# design1.net
KiCad netlist of a schematic drawn in EAGLE
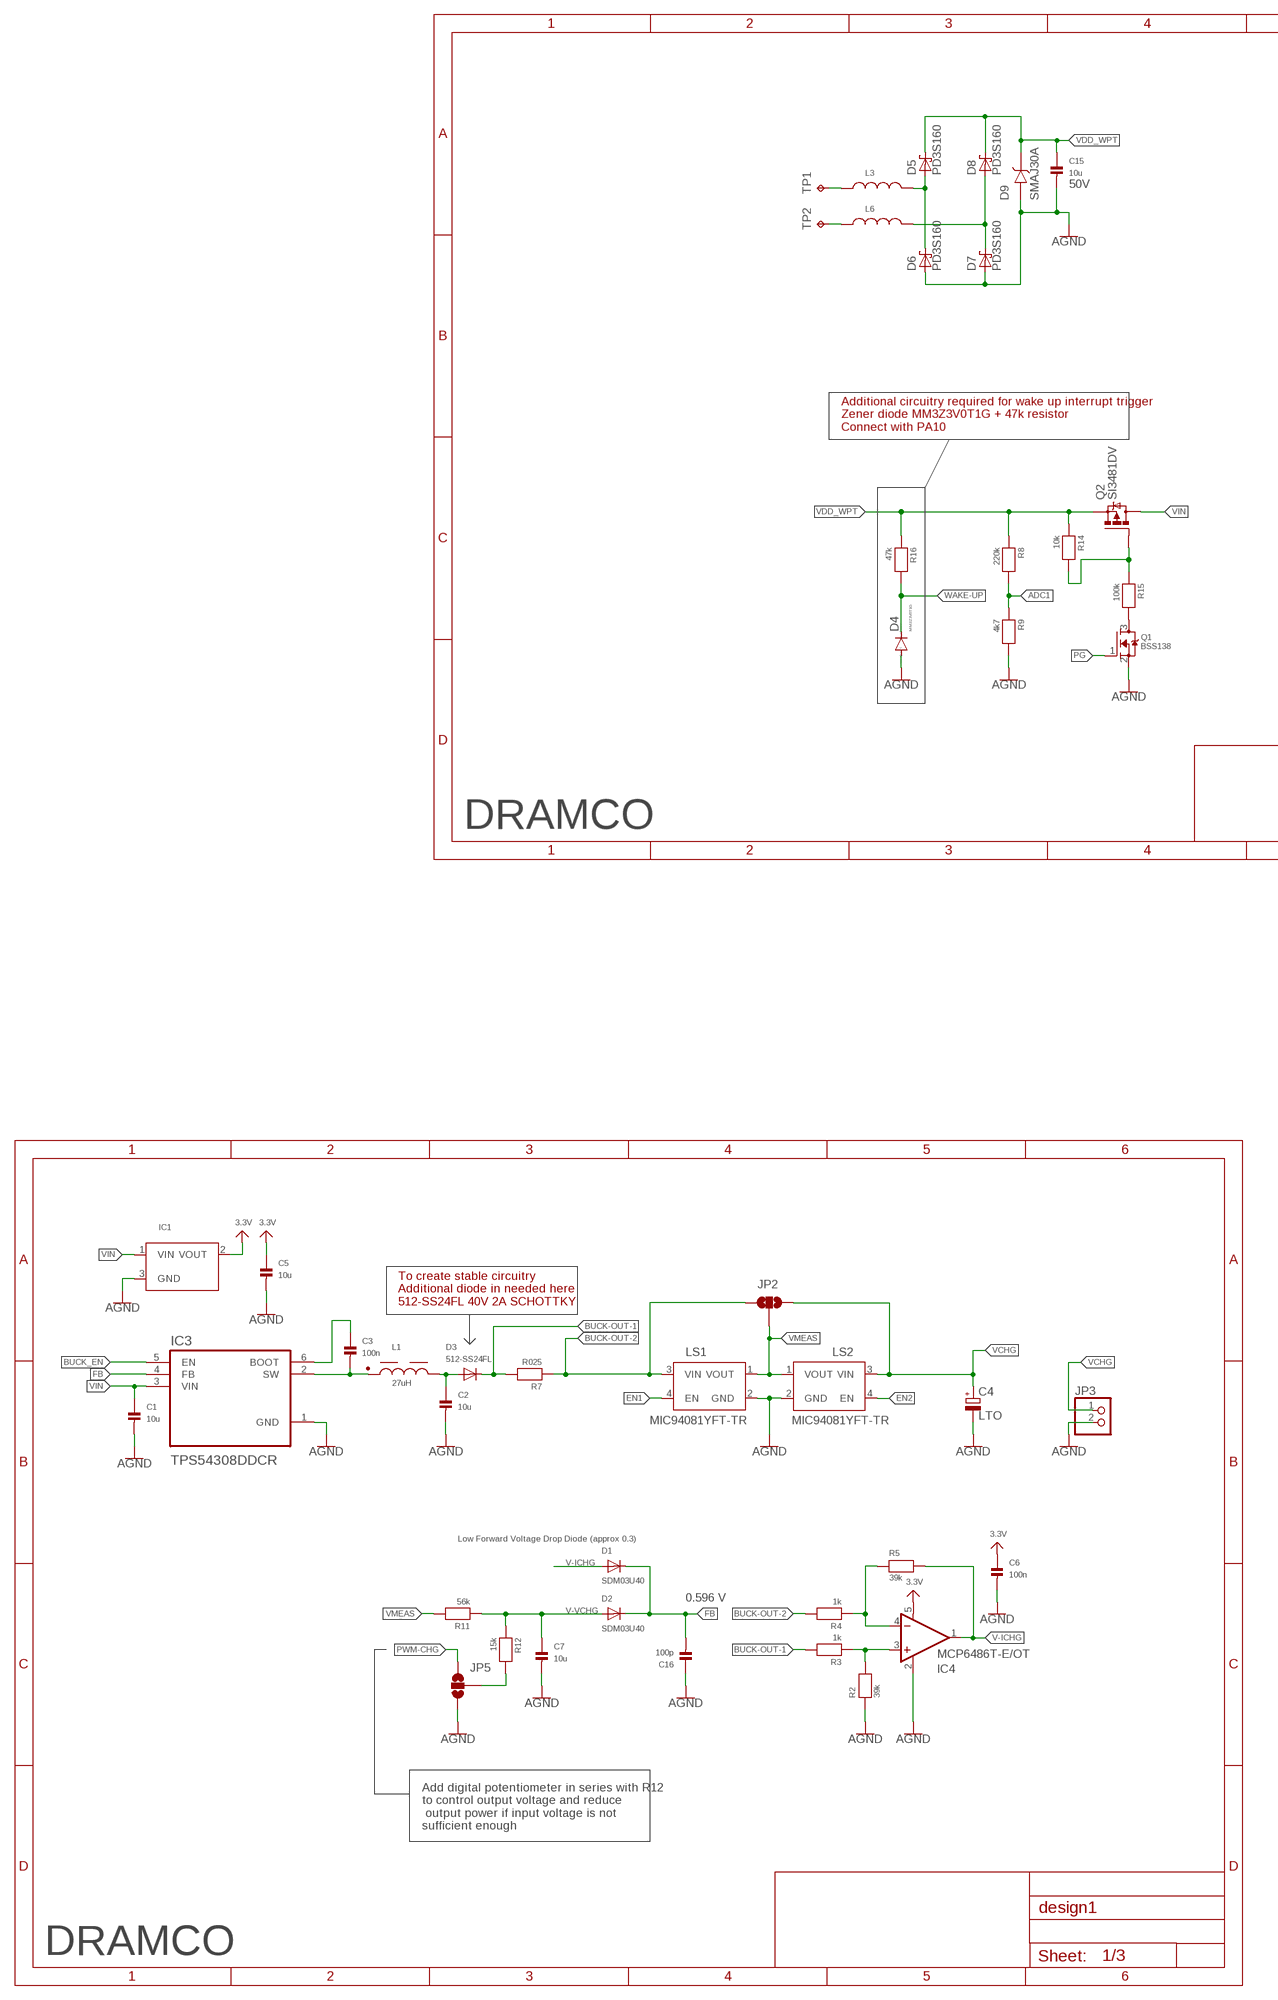
[diagram p0: schematic, sheet 1, part 1 of 2]
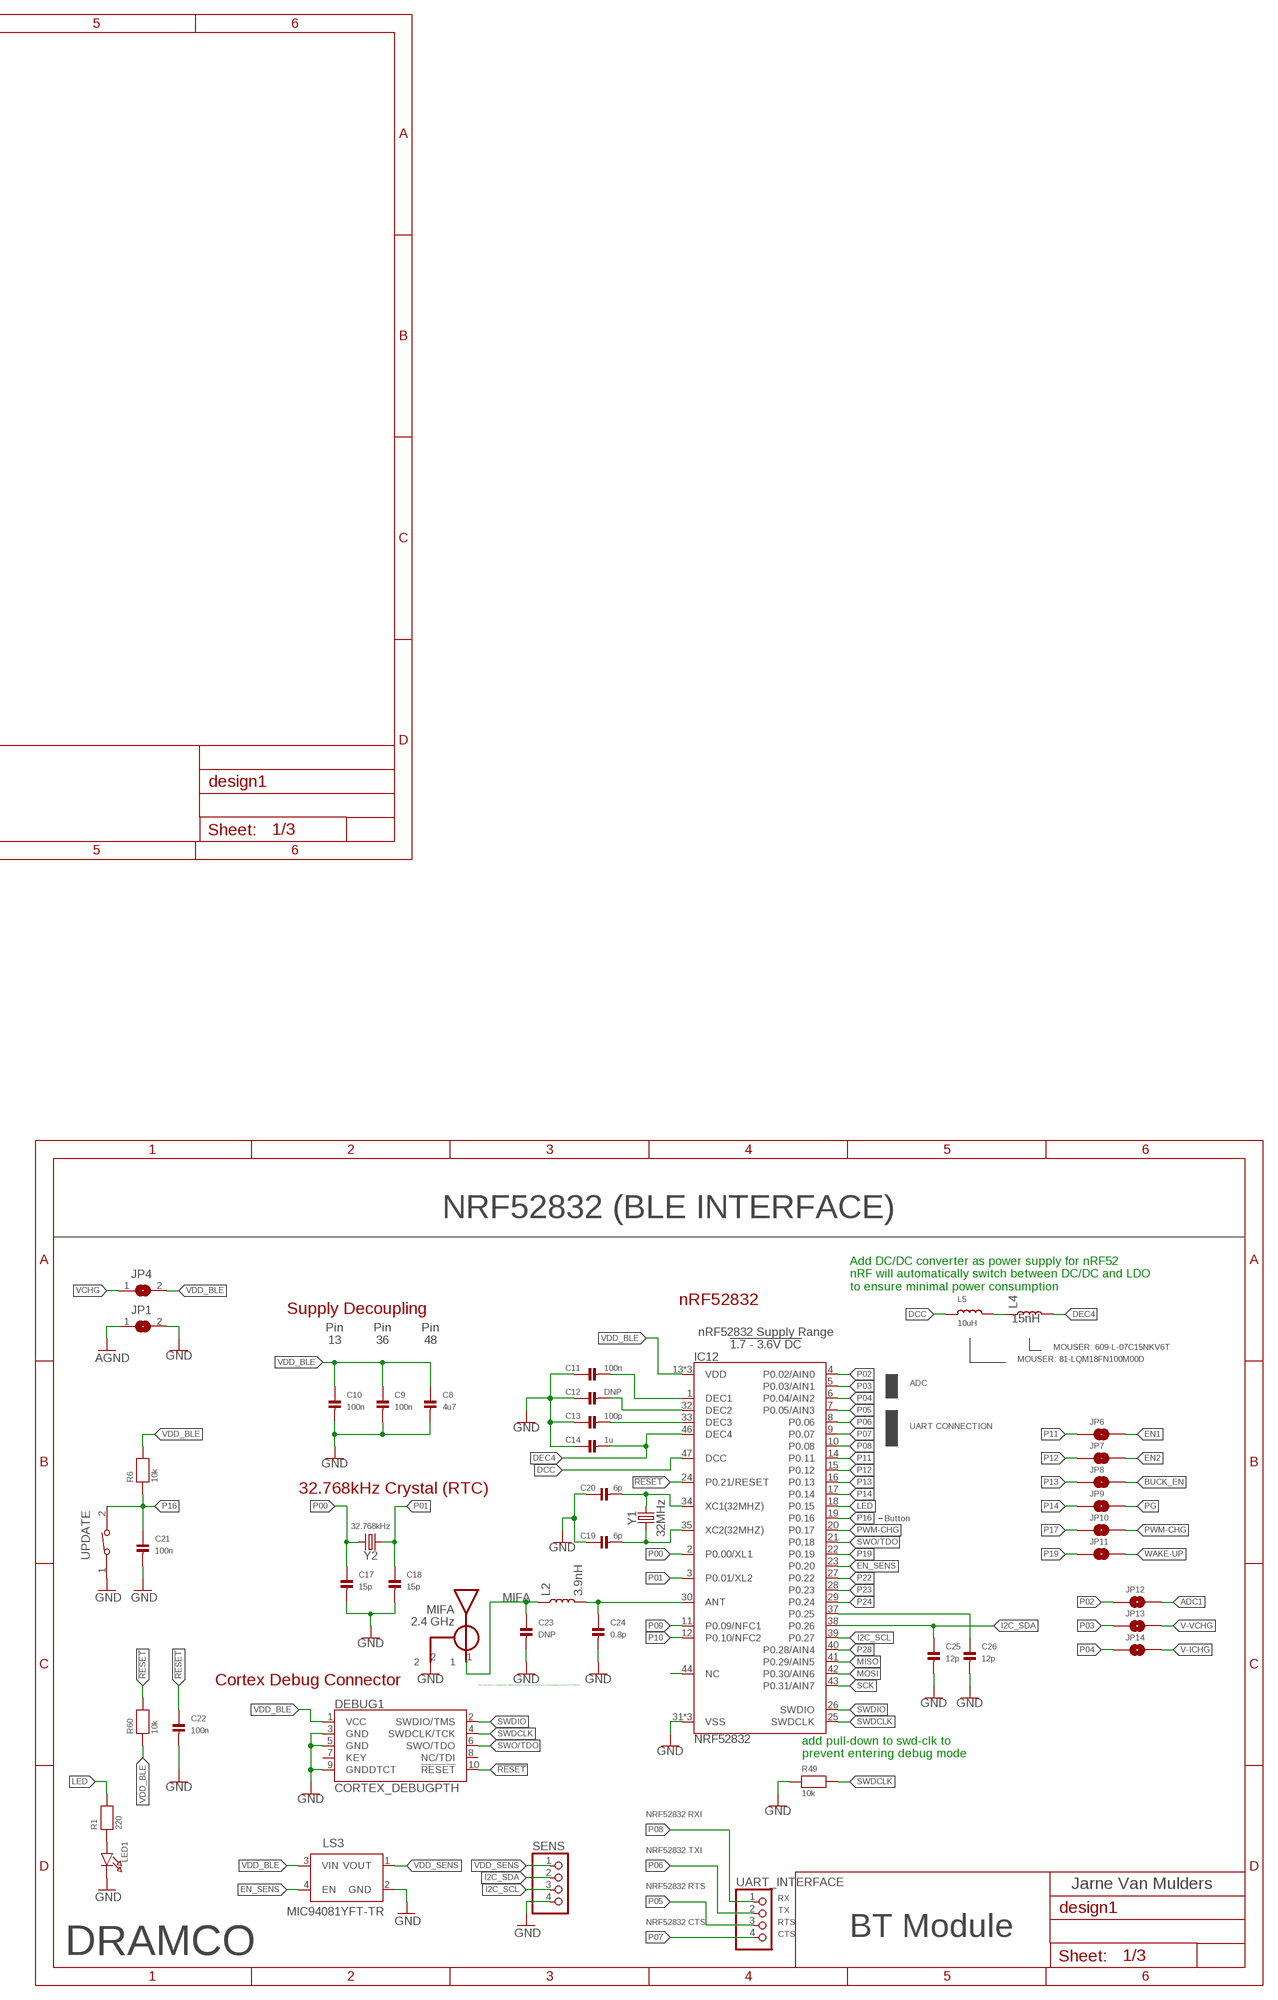
[diagram p1: schematic, sheet 1, part 2 of 2]

(export (version "E")
  (design (tool "Eeschema 10.0.6"))
  (components
    (comp (ref "C1")
      (value "10u")
      (footprint "eagle-import:0603")
      (libsource (lib "eagle-import") (part "CAP_CERAMIC0603"))
    )
    (comp (ref "C2")
      (value "10u")
      (footprint "eagle-import:0603")
      (libsource (lib "eagle-import") (part "CAP_CERAMIC0603"))
    )
    (comp (ref "C3")
      (value "100n")
      (footprint "eagle-import:0603")
      (libsource (lib "eagle-import") (part "CAP_CERAMIC0603"))
    )
    (comp (ref "C4")
      (value "LTO")
      (footprint "eagle-import:E5-10,5")
      (libsource (lib "eagle-import") (part "CPOL-EUE5-10.5"))
    )
    (comp (ref "C5")
      (value "10u")
      (footprint "eagle-import:0603")
      (libsource (lib "eagle-import") (part "CAP_CERAMIC0603"))
    )
    (comp (ref "C6")
      (value "100n")
      (footprint "eagle-import:0402")
      (libsource (lib "eagle-import") (part "CAP_CERAMIC0402"))
    )
    (comp (ref "C7")
      (value "10u")
      (footprint "eagle-import:0603")
      (libsource (lib "eagle-import") (part "CAP_CERAMIC0603"))
    )
    (comp (ref "C8")
      (value "4u7")
      (footprint "eagle-import:0603")
      (libsource (lib "eagle-import") (part "CAP_CERAMIC0603"))
    )
    (comp (ref "C9")
      (value "100n")
      (footprint "eagle-import:0402")
      (libsource (lib "eagle-import") (part "CAP_CERAMIC0402"))
    )
    (comp (ref "C10")
      (value "100n")
      (footprint "eagle-import:0402")
      (libsource (lib "eagle-import") (part "CAP_CERAMIC0402"))
    )
    (comp (ref "C11")
      (value "100n")
      (footprint "eagle-import:0402")
      (libsource (lib "eagle-import") (part "CAP_CERAMIC0402"))
    )
    (comp (ref "C12")
      (value "DNP")
      (footprint "eagle-import:0402")
      (libsource (lib "eagle-import") (part "CAP_CERAMIC0402"))
    )
    (comp (ref "C13")
      (value "100p")
      (footprint "eagle-import:0402")
      (libsource (lib "eagle-import") (part "CAP_CERAMIC0402"))
    )
    (comp (ref "C14")
      (value "1u")
      (footprint "eagle-import:0402")
      (libsource (lib "eagle-import") (part "CAP_CERAMIC0402"))
    )
    (comp (ref "C15")
      (value "10u")
      (footprint "eagle-import:1206")
      (libsource (lib "eagle-import") (part "CAP_CERAMIC1206"))
    )
    (comp (ref "C16")
      (value "100p")
      (footprint "eagle-import:0603")
      (libsource (lib "eagle-import") (part "CAP_CERAMIC0603"))
    )
    (comp (ref "C17")
      (value "15p")
      (footprint "eagle-import:0402")
      (libsource (lib "eagle-import") (part "CAP_CERAMIC0402"))
    )
    (comp (ref "C18")
      (value "15p")
      (footprint "eagle-import:0402")
      (libsource (lib "eagle-import") (part "CAP_CERAMIC0402"))
    )
    (comp (ref "C19")
      (value "6p")
      (footprint "eagle-import:0402")
      (libsource (lib "eagle-import") (part "CAP_CERAMIC0402"))
    )
    (comp (ref "C20")
      (value "6p")
      (footprint "eagle-import:0402")
      (libsource (lib "eagle-import") (part "CAP_CERAMIC0402"))
    )
    (comp (ref "C21")
      (value "100n")
      (footprint "eagle-import:0402")
      (libsource (lib "eagle-import") (part "CAP_CERAMIC0402"))
    )
    (comp (ref "C22")
      (value "100n")
      (footprint "eagle-import:0402")
      (libsource (lib "eagle-import") (part "CAP_CERAMIC0402"))
    )
    (comp (ref "C23")
      (value "DNP")
      (footprint "eagle-import:0402")
      (libsource (lib "eagle-import") (part "CAP_CERAMIC0402"))
    )
    (comp (ref "C24")
      (value "0.8p")
      (footprint "eagle-import:0402")
      (libsource (lib "eagle-import") (part "CAP_CERAMIC0402"))
    )
    (comp (ref "C25")
      (value "12p")
      (footprint "eagle-import:0402")
      (libsource (lib "eagle-import") (part "CAP_CERAMIC0402"))
    )
    (comp (ref "C26")
      (value "12p")
      (footprint "eagle-import:0402")
      (libsource (lib "eagle-import") (part "CAP_CERAMIC0402"))
    )
    (comp (ref "D1")
      (value "SDM03U40")
      (footprint "eagle-import:SOD-523")
      (libsource (lib "eagle-import") (part "DIODESOD-523"))
    )
    (comp (ref "D2")
      (value "SDM03U40")
      (footprint "eagle-import:SOD-523")
      (libsource (lib "eagle-import") (part "DIODESOD-523"))
    )
    (comp (ref "D3")
      (value "512-SS24FL")
      (footprint "eagle-import:SOD-123")
      (libsource (lib "eagle-import") (part "DIODESOD-123"))
    )
    (comp (ref "D4")
      (value "MM3Z3V0T1G")
      (footprint "eagle-import:SOD323-R")
      (libsource (lib "eagle-import") (part "DIODE-SOD323-R"))
    )
    (comp (ref "D5")
      (value "PD3S160")
      (footprint "eagle-import:POWERDI323")
      (libsource (lib "eagle-import") (part "PD3S160"))
    )
    (comp (ref "D6")
      (value "PD3S160")
      (footprint "eagle-import:POWERDI323")
      (libsource (lib "eagle-import") (part "PD3S160"))
    )
    (comp (ref "D7")
      (value "PD3S160")
      (footprint "eagle-import:POWERDI323")
      (libsource (lib "eagle-import") (part "PD3S160"))
    )
    (comp (ref "D8")
      (value "PD3S160")
      (footprint "eagle-import:POWERDI323")
      (libsource (lib "eagle-import") (part "PD3S160"))
    )
    (comp (ref "D9")
      (value "SMAJ30A")
      (footprint "eagle-import:DIOM5026X229N")
      (fields (field (name "MF") "Littelfuse"))
      (libsource (lib "eagle-import") (part "SMAJ30A"))
    )
    (comp (ref "DEBUG1")
      (value "CORTEX_DEBUGPTH")
      (footprint "eagle-import:2X5-PTH-1.27MM")
      (libsource (lib "eagle-import") (part "CORTEX_DEBUGPTH"))
    )
    (comp (ref "IC1")
      (value "VREG_SOT23")
      (footprint "eagle-import:SOT23-R")
      (libsource (lib "eagle-import") (part "VREG_SOT23"))
    )
    (comp (ref "IC3")
      (value "TPS54308DDCR")
      (footprint "eagle-import:SOT95P280X110-6N")
      (fields (field (name "MF") "Texas Instruments"))
      (libsource (lib "eagle-import") (part "TPS54308DDCR"))
    )
    (comp (ref "IC4")
      (value "MCP6486T-E/OT")
      (footprint "eagle-import:SOT23-5")
      (libsource (lib "eagle-import") (part "MCP6291T-E/OT"))
    )
    (comp (ref "IC12")
      (value "NRF52832")
      (footprint "eagle-import:QFN48-6X6MM")
      (libsource (lib "eagle-import") (part "NRF52832"))
    )
    (comp (ref "JP1")
      (value "SOLDERJUMPERREFLOW_NOPASTE")
      (footprint "eagle-import:SOLDERJUMPER_REFLOW_NOPASTE")
      (libsource (lib "eagle-import") (part "SOLDERJUMPERREFLOW_NOPASTE"))
    )
    (comp (ref "JP2")
      (value "JUMPER-SMT_3_NO_NO-SILK")
      (footprint "eagle-import:SMT-JUMPER_3_NO_NO-SILK")
      (libsource (lib "eagle-import") (part "JUMPER-SMT_3_NO_NO-SILK"))
    )
    (comp (ref "JP3")
      (value "HEADER-1X2ROUND")
      (footprint "eagle-import:1X02_ROUND")
      (libsource (lib "eagle-import") (part "HEADER-1X2ROUND"))
    )
    (comp (ref "JP4")
      (value "SOLDERJUMPERREFLOW_NOPASTE")
      (footprint "eagle-import:SOLDERJUMPER_REFLOW_NOPASTE")
      (libsource (lib "eagle-import") (part "SOLDERJUMPERREFLOW_NOPASTE"))
    )
    (comp (ref "JP5")
      (value "JUMPER-SMT_3_NO_NO-SILK")
      (footprint "eagle-import:SMT-JUMPER_3_NO_NO-SILK")
      (libsource (lib "eagle-import") (part "JUMPER-SMT_3_NO_NO-SILK"))
    )
    (comp (ref "JP6")
      (value "JUMPER-SMT_2_NO_NO-SILK")
      (footprint "eagle-import:SMT-JUMPER_2_NO_NO-SILK")
      (libsource (lib "eagle-import") (part "JUMPER-SMT_2_NO_NO-SILK"))
    )
    (comp (ref "JP7")
      (value "JUMPER-SMT_2_NO_NO-SILK")
      (footprint "eagle-import:SMT-JUMPER_2_NO_NO-SILK")
      (libsource (lib "eagle-import") (part "JUMPER-SMT_2_NO_NO-SILK"))
    )
    (comp (ref "JP8")
      (value "JUMPER-SMT_2_NO_NO-SILK")
      (footprint "eagle-import:SMT-JUMPER_2_NO_NO-SILK")
      (libsource (lib "eagle-import") (part "JUMPER-SMT_2_NO_NO-SILK"))
    )
    (comp (ref "JP9")
      (value "JUMPER-SMT_2_NO_NO-SILK")
      (footprint "eagle-import:SMT-JUMPER_2_NO_NO-SILK")
      (libsource (lib "eagle-import") (part "JUMPER-SMT_2_NO_NO-SILK"))
    )
    (comp (ref "JP10")
      (value "JUMPER-SMT_2_NO_NO-SILK")
      (footprint "eagle-import:SMT-JUMPER_2_NO_NO-SILK")
      (libsource (lib "eagle-import") (part "JUMPER-SMT_2_NO_NO-SILK"))
    )
    (comp (ref "JP11")
      (value "JUMPER-SMT_2_NO_NO-SILK")
      (footprint "eagle-import:SMT-JUMPER_2_NO_NO-SILK")
      (libsource (lib "eagle-import") (part "JUMPER-SMT_2_NO_NO-SILK"))
    )
    (comp (ref "JP12")
      (value "JUMPER-SMT_2_NO_NO-SILK")
      (footprint "eagle-import:SMT-JUMPER_2_NO_NO-SILK")
      (libsource (lib "eagle-import") (part "JUMPER-SMT_2_NO_NO-SILK"))
    )
    (comp (ref "JP13")
      (value "JUMPER-SMT_2_NO_NO-SILK")
      (footprint "eagle-import:SMT-JUMPER_2_NO_NO-SILK")
      (libsource (lib "eagle-import") (part "JUMPER-SMT_2_NO_NO-SILK"))
    )
    (comp (ref "JP14")
      (value "JUMPER-SMT_2_NO_NO-SILK")
      (footprint "eagle-import:SMT-JUMPER_2_NO_NO-SILK")
      (libsource (lib "eagle-import") (part "JUMPER-SMT_2_NO_NO-SILK"))
    )
    (comp (ref "L1")
      (value "27uH")
      (footprint "eagle-import:WE-PD_7332_7345_PLASTIC_BASE")
      (libsource (lib "eagle-import") (part "WE-PD_7332_PLASTIC_7447789127"))
    )
    (comp (ref "L2")
      (value "3.9nH")
      (footprint "eagle-import:0402")
      (libsource (lib "eagle-import") (part "INDUCTOR-0402-3.9NH"))
    )
    (comp (ref "L3")
      (value "WE-CAIR_4248_744912182")
      (footprint "eagle-import:WE-CAIR_4248")
      (libsource (lib "eagle-import") (part "WE-CAIR_4248_744912182"))
    )
    (comp (ref "L4")
      (value "15nH")
      (footprint "eagle-import:0402")
      (libsource (lib "eagle-import") (part "INDUCTOR-0402-3.9NH"))
    )
    (comp (ref "L5")
      (value "10uH")
      (footprint "eagle-import:_0603MP")
      (libsource (lib "eagle-import") (part "INDUCTOR_0603MP"))
    )
    (comp (ref "L6")
      (value "WE-CAIR_4248_744912182")
      (footprint "eagle-import:WE-CAIR_4248")
      (libsource (lib "eagle-import") (part "WE-CAIR_4248_744912182"))
    )
    (comp (ref "LED1")
      (value "LED0805")
      (footprint "eagle-import:CHIPLED_0805")
      (libsource (lib "eagle-import") (part "LED0805"))
    )
    (comp (ref "LS1")
      (value "MIC94081YFT-TR")
      (footprint "eagle-import:IC_MIC94081YFT-TR")
      (fields (field (name "MF") "Microchip"))
      (libsource (lib "eagle-import") (part "MIC94081YFT-TR"))
    )
    (comp (ref "LS2")
      (value "MIC94081YFT-TR")
      (footprint "eagle-import:IC_MIC94081YFT-TR")
      (fields (field (name "MF") "Microchip"))
      (libsource (lib "eagle-import") (part "MIC94081YFT-TR"))
    )
    (comp (ref "LS3")
      (value "MIC94081YFT-TR")
      (footprint "eagle-import:IC_MIC94081YFT-TR")
      (fields (field (name "MF") "Microchip"))
      (libsource (lib "eagle-import") (part "MIC94081YFT-TR"))
    )
    (comp (ref "Q1")
      (value "BSS138")
      (footprint "eagle-import:SOT23-R")
      (libsource (lib "eagle-import") (part "MOSFET-NREFLOW"))
    )
    (comp (ref "Q2")
      (value "SI3481DV")
      (footprint "eagle-import:TSOP-6.PAC")
      (libsource (lib "eagle-import") (part "SI3481DV"))
    )
    (comp (ref "R1")
      (value "220")
      (footprint "eagle-import:0603")
      (libsource (lib "eagle-import") (part "RESISTOR0603"))
    )
    (comp (ref "R2")
      (value "39k")
      (footprint "eagle-import:0603")
      (libsource (lib "eagle-import") (part "RESISTOR0603"))
    )
    (comp (ref "R3")
      (value "1k")
      (footprint "eagle-import:0603")
      (libsource (lib "eagle-import") (part "RESISTOR0603"))
    )
    (comp (ref "R4")
      (value "1k")
      (footprint "eagle-import:0603")
      (libsource (lib "eagle-import") (part "RESISTOR0603"))
    )
    (comp (ref "R5")
      (value "39k")
      (footprint "eagle-import:0603")
      (libsource (lib "eagle-import") (part "RESISTOR0603"))
    )
    (comp (ref "R6")
      (value "10k")
      (footprint "eagle-import:0402")
      (libsource (lib "eagle-import") (part "RESISTOR0402"))
    )
    (comp (ref "R7")
      (value "R025")
      (footprint "eagle-import:0603")
      (libsource (lib "eagle-import") (part "RESISTOR0603"))
    )
    (comp (ref "R8")
      (value "220k")
      (footprint "eagle-import:0603")
      (libsource (lib "eagle-import") (part "RESISTOR0603"))
    )
    (comp (ref "R9")
      (value "4k7")
      (footprint "eagle-import:0603")
      (libsource (lib "eagle-import") (part "RESISTOR0603"))
    )
    (comp (ref "R11")
      (value "56k")
      (footprint "eagle-import:0603")
      (libsource (lib "eagle-import") (part "RESISTOR0603"))
    )
    (comp (ref "R12")
      (value "15k")
      (footprint "eagle-import:0603")
      (libsource (lib "eagle-import") (part "RESISTOR0603"))
    )
    (comp (ref "R14")
      (value "10k")
      (footprint "eagle-import:0603")
      (libsource (lib "eagle-import") (part "RESISTOR0603"))
    )
    (comp (ref "R15")
      (value "100k")
      (footprint "eagle-import:0603")
      (libsource (lib "eagle-import") (part "RESISTOR0603"))
    )
    (comp (ref "R16")
      (value "47k")
      (footprint "eagle-import:0603")
      (libsource (lib "eagle-import") (part "RESISTOR0603"))
    )
    (comp (ref "R49")
      (value "10k")
      (footprint "eagle-import:0402")
      (libsource (lib "eagle-import") (part "RESISTOR0402"))
    )
    (comp (ref "R60")
      (value "10k")
      (footprint "eagle-import:0402")
      (libsource (lib "eagle-import") (part "RESISTOR0402"))
    )
    (comp (ref "SENS")
      (value "HEADER-1X4ROUND")
      (footprint "eagle-import:1X04_ROUND")
      (libsource (lib "eagle-import") (part "HEADER-1X4ROUND"))
    )
    (comp (ref "TP1")
      (value "TPTP20SQ")
      (footprint "eagle-import:TP20SQ")
      (libsource (lib "eagle-import") (part "TPTP20SQ"))
    )
    (comp (ref "TP2")
      (value "TPTP20SQ")
      (footprint "eagle-import:TP20SQ")
      (libsource (lib "eagle-import") (part "TPTP20SQ"))
    )
    (comp (ref "U$18")
      (value "BLE-ANT")
      (footprint "eagle-import:ANT-2G4")
      (libsource (lib "eagle-import") (part "BLE-ANT"))
    )
    (comp (ref "UART_INTERFACE")
      (value "HEADER-1X4ROUND")
      (footprint "eagle-import:1X04_ROUND")
      (libsource (lib "eagle-import") (part "HEADER-1X4ROUND"))
    )
    (comp (ref "UPDATE")
      (value "434111043826")
      (footprint "eagle-import:434111043826")
      (libsource (lib "eagle-import") (part "434111043826"))
    )
    (comp (ref "Y1")
      (value "32MHz")
      (footprint "eagle-import:CRYSTAL-SMD-2.0X1.6MM")
      (libsource (lib "eagle-import") (part "CRYSTAL-32MHZ-SMD-2.0X1.6MM"))
    )
    (comp (ref "Y2")
      (value "32.768kHz")
      (footprint "eagle-import:CRYSTAL-SMD-3.2X1.5MM")
      (libsource (lib "eagle-import") (part "CRYSTAL-32.768KHZSMD-3.2X1.5"))
    )
  )
  (nets
    (net (code "1") (name "3.3V") (class "Default")
      (node (ref "C5") (pin "1") (pinfunction "P$1_1") (pintype "passive"))
      (node (ref "C6") (pin "1") (pinfunction "P$1_1") (pintype "passive"))
      (node (ref "IC1") (pin "2") (pinfunction "VOUT_2") (pintype "power_in"))
      (node (ref "IC4") (pin "5") (pinfunction "V+_5") (pintype "power_in"))
    )
    (net (code "2") (name "ADC1") (class "Default")
      (node (ref "JP12") (pin "2") (pinfunction "2_2") (pintype "passive"))
      (node (ref "R8") (pin "2") (pinfunction "2_2") (pintype "passive"))
      (node (ref "R9") (pin "1") (pinfunction "1_1") (pintype "passive"))
    )
    (net (code "3") (name "AGND") (class "Default")
      (node (ref "C1") (pin "2") (pinfunction "P$2_2") (pintype "passive"))
      (node (ref "C15") (pin "2") (pinfunction "P$2_2") (pintype "passive"))
      (node (ref "C16") (pin "1") (pinfunction "P$1_1") (pintype "passive"))
      (node (ref "C2") (pin "2") (pinfunction "P$2_2") (pintype "passive"))
      (node (ref "C4") (pin "-") (pinfunction "-_-") (pintype "passive"))
      (node (ref "C5") (pin "2") (pinfunction "P$2_2") (pintype "passive"))
      (node (ref "C6") (pin "2") (pinfunction "P$2_2") (pintype "passive"))
      (node (ref "C7") (pin "2") (pinfunction "P$2_2") (pintype "passive"))
      (node (ref "D4") (pin "A") (pinfunction "A_A") (pintype "passive"))
      (node (ref "D6") (pin "A") (pinfunction "A_A") (pintype "passive"))
      (node (ref "D7") (pin "A") (pinfunction "A_A") (pintype "passive"))
      (node (ref "D9") (pin "A") (pinfunction "A_A") (pintype "passive"))
      (node (ref "IC1") (pin "3") (pinfunction "GND_3") (pintype "power_in"))
      (node (ref "IC3") (pin "1") (pinfunction "GND_1") (pintype "power_in"))
      (node (ref "IC4") (pin "2") (pinfunction "V-_2") (pintype "power_in"))
      (node (ref "JP1") (pin "1") (pinfunction "1_1") (pintype "passive"))
      (node (ref "JP3") (pin "2") (pinfunction "2_2") (pintype "passive"))
      (node (ref "JP5") (pin "1") (pinfunction "1_1") (pintype "passive"))
      (node (ref "LS1") (pin "2") (pinfunction "GND_2") (pintype "power_in"))
      (node (ref "LS2") (pin "2") (pinfunction "GND_2") (pintype "power_in"))
      (node (ref "Q1") (pin "2") (pinfunction "S_2") (pintype "bidirectional"))
      (node (ref "R2") (pin "1") (pinfunction "1_1") (pintype "passive"))
      (node (ref "R9") (pin "2") (pinfunction "2_2") (pintype "passive"))
    )
    (net (code "4") (name "BUCK-OUT-1") (class "Default")
      (node (ref "D3") (pin "C") (pinfunction "C_C") (pintype "passive"))
      (node (ref "R3") (pin "2") (pinfunction "2_2") (pintype "passive"))
      (node (ref "R7") (pin "2") (pinfunction "2_2") (pintype "passive"))
    )
    (net (code "5") (name "BUCK-OUT-2") (class "Default")
      (node (ref "JP2") (pin "1") (pinfunction "1_1") (pintype "passive"))
      (node (ref "LS1") (pin "3") (pinfunction "VIN_3") (pintype "input"))
      (node (ref "R4") (pin "2") (pinfunction "2_2") (pintype "passive"))
      (node (ref "R7") (pin "1") (pinfunction "1_1") (pintype "passive"))
    )
    (net (code "6") (name "BUCK_EN") (class "Default")
      (node (ref "IC3") (pin "5") (pinfunction "EN_5") (pintype "input"))
      (node (ref "JP8") (pin "2") (pinfunction "2_2") (pintype "passive"))
    )
    (net (code "7") (name "DCC") (class "Default")
      (node (ref "IC12") (pin "47") (pinfunction "DCC_47") (pintype "bidirectional"))
      (node (ref "L5") (pin "1") (pinfunction "1_1") (pintype "passive"))
    )
    (net (code "8") (name "DEC4") (class "Default")
      (node (ref "C14") (pin "2") (pinfunction "P$2_2") (pintype "passive"))
      (node (ref "IC12") (pin "46") (pinfunction "DEC4_46") (pintype "bidirectional"))
      (node (ref "L4") (pin "2") (pinfunction "2_2") (pintype "passive"))
    )
    (net (code "9") (name "EN1") (class "Default")
      (node (ref "JP6") (pin "2") (pinfunction "2_2") (pintype "passive"))
      (node (ref "LS1") (pin "4") (pinfunction "EN_4") (pintype "input"))
    )
    (net (code "10") (name "EN2") (class "Default")
      (node (ref "JP7") (pin "2") (pinfunction "2_2") (pintype "passive"))
      (node (ref "LS2") (pin "4") (pinfunction "EN_4") (pintype "input"))
    )
    (net (code "11") (name "EN_SENS") (class "Default")
      (node (ref "IC12") (pin "23") (pinfunction "P0.20_23") (pintype "bidirectional"))
      (node (ref "LS3") (pin "4") (pinfunction "EN_4") (pintype "input"))
    )
    (net (code "12") (name "FB") (class "Default")
      (node (ref "C16") (pin "2") (pinfunction "P$2_2") (pintype "passive"))
      (node (ref "D1") (pin "K") (pinfunction "C_K") (pintype "passive"))
      (node (ref "D2") (pin "K") (pinfunction "C_K") (pintype "passive"))
      (node (ref "IC3") (pin "4") (pinfunction "FB_4") (pintype "input"))
    )
    (net (code "13") (name "GND") (class "Default")
      (node (ref "C10") (pin "2") (pinfunction "P$2_2") (pintype "passive"))
      (node (ref "C11") (pin "1") (pinfunction "P$1_1") (pintype "passive"))
      (node (ref "C12") (pin "1") (pinfunction "P$1_1") (pintype "passive"))
      (node (ref "C13") (pin "1") (pinfunction "P$1_1") (pintype "passive"))
      (node (ref "C14") (pin "1") (pinfunction "P$1_1") (pintype "passive"))
      (node (ref "C17") (pin "2") (pinfunction "P$2_2") (pintype "passive"))
      (node (ref "C18") (pin "2") (pinfunction "P$2_2") (pintype "passive"))
      (node (ref "C19") (pin "1") (pinfunction "P$1_1") (pintype "passive"))
      (node (ref "C20") (pin "1") (pinfunction "P$1_1") (pintype "passive"))
      (node (ref "C21") (pin "2") (pinfunction "P$2_2") (pintype "passive"))
      (node (ref "C22") (pin "2") (pinfunction "P$2_2") (pintype "passive"))
      (node (ref "C23") (pin "2") (pinfunction "P$2_2") (pintype "passive"))
      (node (ref "C24") (pin "2") (pinfunction "P$2_2") (pintype "passive"))
      (node (ref "C25") (pin "2") (pinfunction "P$2_2") (pintype "passive"))
      (node (ref "C26") (pin "2") (pinfunction "P$2_2") (pintype "passive"))
      (node (ref "C8") (pin "2") (pinfunction "P$2_2") (pintype "passive"))
      (node (ref "C9") (pin "2") (pinfunction "P$2_2") (pintype "passive"))
      (node (ref "DEBUG1") (pin "3") (pinfunction "GND_3") (pintype "bidirectional"))
      (node (ref "DEBUG1") (pin "5") (pinfunction "GND_5") (pintype "bidirectional"))
      (node (ref "DEBUG1") (pin "9") (pinfunction "GNDDTCT_9") (pintype "bidirectional"))
      (node (ref "IC12") (pin "31") (pinfunction "VSS_31") (pintype "bidirectional"))
      (node (ref "IC12") (pin "45") (pinfunction "VSS_45") (pintype "bidirectional"))
      (node (ref "IC12") (pin "EP") (pinfunction "VSS_EP") (pintype "bidirectional"))
      (node (ref "JP1") (pin "2") (pinfunction "2_2") (pintype "passive"))
      (node (ref "LED1") (pin "C") (pinfunction "C_C") (pintype "passive"))
      (node (ref "LS3") (pin "2") (pinfunction "GND_2") (pintype "power_in"))
      (node (ref "R49") (pin "1") (pinfunction "1_1") (pintype "passive"))
      (node (ref "SENS") (pin "4") (pinfunction "4_4") (pintype "passive"))
      (node (ref "U$18") (pin "2") (pinfunction "2_2") (pintype "bidirectional"))
      (node (ref "UPDATE") (pin "1") (pinfunction "1_1") (pintype "passive"))
    )
    (net (code "14") (name "I2C_SCL") (class "Default")
      (node (ref "IC12") (pin "39") (pinfunction "P0.27_39") (pintype "bidirectional"))
      (node (ref "SENS") (pin "3") (pinfunction "3_3") (pintype "passive"))
    )
    (net (code "15") (name "I2C_SDA") (class "Default")
      (node (ref "C25") (pin "1") (pinfunction "P$1_1") (pintype "passive"))
      (node (ref "IC12") (pin "38") (pinfunction "P0.26_38") (pintype "bidirectional"))
      (node (ref "SENS") (pin "2") (pinfunction "2_2") (pintype "passive"))
    )
    (net (code "16") (name "LED") (class "Default")
      (node (ref "IC12") (pin "18") (pinfunction "P0.15_18") (pintype "bidirectional"))
      (node (ref "R1") (pin "2") (pinfunction "2_2") (pintype "passive"))
    )
    (net (code "17") (name "MIFA") (class "Default")
      (node (ref "C23") (pin "1") (pinfunction "P$1_1") (pintype "passive"))
      (node (ref "L2") (pin "1") (pinfunction "1_1") (pintype "passive"))
      (node (ref "U$18") (pin "1") (pinfunction "1_1") (pintype "bidirectional"))
    )
    (net (code "18") (name "MISO") (class "Default")
      (node (ref "IC12") (pin "41") (pinfunction "P0.29/AIN5_41") (pintype "bidirectional"))
    )
    (net (code "19") (name "MOSI") (class "Default")
      (node (ref "IC12") (pin "42") (pinfunction "P0.30/AIN6_42") (pintype "bidirectional"))
    )
    (net (code "20") (name "Net-(C2-P$1)") (class "Default")
      (node (ref "C2") (pin "1") (pinfunction "P$1_1") (pintype "passive"))
      (node (ref "D3") (pin "A") (pinfunction "A_A") (pintype "passive"))
      (node (ref "L1") (pin "2") (pinfunction "2_2") (pintype "passive"))
    )
    (net (code "21") (name "Net-(C3-P$1)") (class "Default")
      (node (ref "C3") (pin "1") (pinfunction "P$1_1") (pintype "passive"))
      (node (ref "IC3") (pin "6") (pinfunction "BOOT_6") (pintype "output"))
    )
    (net (code "22") (name "Net-(C3-P$2)") (class "Default")
      (node (ref "C3") (pin "2") (pinfunction "P$2_2") (pintype "passive"))
      (node (ref "IC3") (pin "2") (pinfunction "SW_2") (pintype "output"))
      (node (ref "L1") (pin "1") (pinfunction "1_1") (pintype "passive"))
    )
    (net (code "23") (name "Net-(C11-P$2)") (class "Default")
      (node (ref "C11") (pin "2") (pinfunction "P$2_2") (pintype "passive"))
      (node (ref "IC12") (pin "1") (pinfunction "DEC1_1") (pintype "bidirectional"))
    )
    (net (code "24") (name "Net-(C12-P$2)") (class "Default")
      (node (ref "C12") (pin "2") (pinfunction "P$2_2") (pintype "passive"))
      (node (ref "IC12") (pin "32") (pinfunction "DEC2_32") (pintype "bidirectional"))
    )
    (net (code "25") (name "Net-(C13-P$2)") (class "Default")
      (node (ref "C13") (pin "2") (pinfunction "P$2_2") (pintype "passive"))
      (node (ref "IC12") (pin "33") (pinfunction "DEC3_33") (pintype "bidirectional"))
    )
    (net (code "26") (name "Net-(C19-P$2)") (class "Default")
      (node (ref "C19") (pin "2") (pinfunction "P$2_2") (pintype "passive"))
      (node (ref "IC12") (pin "35") (pinfunction "XC2(32MHZ)_35") (pintype "bidirectional"))
      (node (ref "Y1") (pin "1") (pinfunction "1_1") (pintype "passive"))
    )
    (net (code "27") (name "Net-(C20-P$2)") (class "Default")
      (node (ref "C20") (pin "2") (pinfunction "P$2_2") (pintype "passive"))
      (node (ref "IC12") (pin "34") (pinfunction "XC1(32MHZ)_34") (pintype "bidirectional"))
      (node (ref "Y1") (pin "3") (pinfunction "2_3") (pintype "passive"))
    )
    (net (code "28") (name "Net-(C24-P$1)") (class "Default")
      (node (ref "C24") (pin "1") (pinfunction "P$1_1") (pintype "passive"))
      (node (ref "IC12") (pin "30") (pinfunction "ANT_30") (pintype "bidirectional"))
      (node (ref "L2") (pin "2") (pinfunction "2_2") (pintype "passive"))
    )
    (net (code "29") (name "Net-(C26-P$1)") (class "Default")
      (node (ref "C26") (pin "1") (pinfunction "P$1_1") (pintype "passive"))
      (node (ref "IC12") (pin "37") (pinfunction "P0.25_37") (pintype "bidirectional"))
    )
    (net (code "30") (name "Net-(D5-PadA)") (class "Default")
      (node (ref "D5") (pin "A") (pinfunction "A_A") (pintype "passive"))
      (node (ref "D6") (pin "C") (pinfunction "C_C") (pintype "passive"))
      (node (ref "L3") (pin "2") (pinfunction "2_2") (pintype "passive"))
    )
    (net (code "31") (name "Net-(D7-PadC)") (class "Default")
      (node (ref "D7") (pin "C") (pinfunction "C_C") (pintype "passive"))
      (node (ref "D8") (pin "A") (pinfunction "A_A") (pintype "passive"))
      (node (ref "L6") (pin "2") (pinfunction "2_2") (pintype "passive"))
    )
    (net (code "32") (name "Net-(IC4-+IN)") (class "Default")
      (node (ref "IC4") (pin "3") (pinfunction "+IN_3") (pintype "input"))
      (node (ref "R2") (pin "2") (pinfunction "2_2") (pintype "passive"))
      (node (ref "R3") (pin "1") (pinfunction "1_1") (pintype "passive"))
    )
    (net (code "33") (name "Net-(IC4--IN)") (class "Default")
      (node (ref "IC4") (pin "4") (pinfunction "-IN_4") (pintype "input"))
      (node (ref "R4") (pin "1") (pinfunction "1_1") (pintype "passive"))
      (node (ref "R5") (pin "1") (pinfunction "1_1") (pintype "passive"))
    )
    (net (code "34") (name "Net-(JP5-Pad2)") (class "Default")
      (node (ref "JP5") (pin "2") (pinfunction "2_2") (pintype "passive"))
      (node (ref "R12") (pin "2") (pinfunction "2_2") (pintype "passive"))
    )
    (net (code "35") (name "Net-(L3-Pad1)") (class "Default")
      (node (ref "L3") (pin "1") (pinfunction "1_1") (pintype "passive"))
      (node (ref "TP1") (pin "TP") (pinfunction "TP_TP") (pintype "input"))
    )
    (net (code "36") (name "Net-(L4-Pad1)") (class "Default")
      (node (ref "L4") (pin "1") (pinfunction "1_1") (pintype "passive"))
      (node (ref "L5") (pin "2") (pinfunction "2_2") (pintype "passive"))
    )
    (net (code "37") (name "Net-(L6-Pad1)") (class "Default")
      (node (ref "L6") (pin "1") (pinfunction "1_1") (pintype "passive"))
      (node (ref "TP2") (pin "TP") (pinfunction "TP_TP") (pintype "input"))
    )
    (net (code "38") (name "Net-(LED1-PadA)") (class "Default")
      (node (ref "LED1") (pin "A") (pinfunction "A_A") (pintype "passive"))
      (node (ref "R1") (pin "1") (pinfunction "1_1") (pintype "passive"))
    )
    (net (code "39") (name "Net-(Q1-D)") (class "Default")
      (node (ref "Q1") (pin "3") (pinfunction "D_3") (pintype "bidirectional"))
      (node (ref "R15") (pin "2") (pinfunction "2_2") (pintype "passive"))
    )
    (net (code "40") (name "Net-(Q2-G)") (class "Default")
      (node (ref "Q2") (pin "3") (pinfunction "G_3") (pintype "passive"))
      (node (ref "R14") (pin "2") (pinfunction "2_2") (pintype "passive"))
      (node (ref "R15") (pin "1") (pinfunction "1_1") (pintype "passive"))
    )
    (net (code "41") (name "P00") (class "Default")
      (node (ref "C17") (pin "1") (pinfunction "P$1_1") (pintype "passive"))
      (node (ref "IC12") (pin "2") (pinfunction "P0.00/XL1_2") (pintype "bidirectional"))
      (node (ref "Y2") (pin "P$2") (pinfunction "2_P$2") (pintype "passive"))
    )
    (net (code "42") (name "P01") (class "Default")
      (node (ref "C18") (pin "1") (pinfunction "P$1_1") (pintype "passive"))
      (node (ref "IC12") (pin "3") (pinfunction "P0.01/XL2_3") (pintype "bidirectional"))
      (node (ref "Y2") (pin "P$1") (pinfunction "1_P$1") (pintype "passive"))
    )
    (net (code "43") (name "P02") (class "Default")
      (node (ref "IC12") (pin "4") (pinfunction "P0.02/AIN0_4") (pintype "bidirectional"))
      (node (ref "JP12") (pin "1") (pinfunction "1_1") (pintype "passive"))
    )
    (net (code "44") (name "P03") (class "Default")
      (node (ref "IC12") (pin "5") (pinfunction "P0.03/AIN1_5") (pintype "bidirectional"))
      (node (ref "JP13") (pin "1") (pinfunction "1_1") (pintype "passive"))
    )
    (net (code "45") (name "P04") (class "Default")
      (node (ref "IC12") (pin "6") (pinfunction "P0.04/AIN2_6") (pintype "bidirectional"))
      (node (ref "JP14") (pin "1") (pinfunction "1_1") (pintype "passive"))
    )
    (net (code "46") (name "P05") (class "Default")
      (node (ref "IC12") (pin "7") (pinfunction "P0.05/AIN3_7") (pintype "bidirectional"))
      (node (ref "UART_INTERFACE") (pin "3") (pinfunction "3_3") (pintype "passive"))
    )
    (net (code "47") (name "P06") (class "Default")
      (node (ref "IC12") (pin "8") (pinfunction "P0.06_8") (pintype "bidirectional"))
      (node (ref "UART_INTERFACE") (pin "2") (pinfunction "2_2") (pintype "passive"))
    )
    (net (code "48") (name "P07") (class "Default")
      (node (ref "IC12") (pin "9") (pinfunction "P0.07_9") (pintype "bidirectional"))
      (node (ref "UART_INTERFACE") (pin "4") (pinfunction "4_4") (pintype "passive"))
    )
    (net (code "49") (name "P08") (class "Default")
      (node (ref "IC12") (pin "10") (pinfunction "P0.08_10") (pintype "bidirectional"))
      (node (ref "UART_INTERFACE") (pin "1") (pinfunction "1_1") (pintype "passive"))
    )
    (net (code "50") (name "P09") (class "Default")
      (node (ref "IC12") (pin "11") (pinfunction "P0.09/NFC1_11") (pintype "bidirectional"))
    )
    (net (code "51") (name "P10") (class "Default")
      (node (ref "IC12") (pin "12") (pinfunction "P0.10/NFC2_12") (pintype "bidirectional"))
    )
    (net (code "52") (name "P11") (class "Default")
      (node (ref "IC12") (pin "14") (pinfunction "P0.11_14") (pintype "bidirectional"))
      (node (ref "JP6") (pin "1") (pinfunction "1_1") (pintype "passive"))
    )
    (net (code "53") (name "P12") (class "Default")
      (node (ref "IC12") (pin "15") (pinfunction "P0.12_15") (pintype "bidirectional"))
      (node (ref "JP7") (pin "1") (pinfunction "1_1") (pintype "passive"))
    )
    (net (code "54") (name "P13") (class "Default")
      (node (ref "IC12") (pin "16") (pinfunction "P0.13_16") (pintype "bidirectional"))
      (node (ref "JP8") (pin "1") (pinfunction "1_1") (pintype "passive"))
    )
    (net (code "55") (name "P14") (class "Default")
      (node (ref "IC12") (pin "17") (pinfunction "P0.14_17") (pintype "bidirectional"))
      (node (ref "JP9") (pin "1") (pinfunction "1_1") (pintype "passive"))
    )
    (net (code "56") (name "P16") (class "Default")
      (node (ref "C21") (pin "1") (pinfunction "P$1_1") (pintype "passive"))
      (node (ref "IC12") (pin "19") (pinfunction "P0.16_19") (pintype "bidirectional"))
      (node (ref "R6") (pin "1") (pinfunction "1_1") (pintype "passive"))
      (node (ref "UPDATE") (pin "2") (pinfunction "2_2") (pintype "passive"))
    )
    (net (code "57") (name "P17") (class "Default")
      (node (ref "JP10") (pin "1") (pinfunction "1_1") (pintype "passive"))
    )
    (net (code "58") (name "P19") (class "Default")
      (node (ref "IC12") (pin "22") (pinfunction "P0.19_22") (pintype "bidirectional"))
      (node (ref "JP11") (pin "1") (pinfunction "1_1") (pintype "passive"))
    )
    (net (code "59") (name "P22") (class "Default")
      (node (ref "IC12") (pin "27") (pinfunction "P0.22_27") (pintype "bidirectional"))
    )
    (net (code "60") (name "P23") (class "Default")
      (node (ref "IC12") (pin "28") (pinfunction "P0.23_28") (pintype "bidirectional"))
    )
    (net (code "61") (name "P24") (class "Default")
      (node (ref "IC12") (pin "29") (pinfunction "P0.24_29") (pintype "bidirectional"))
    )
    (net (code "62") (name "P28") (class "Default")
      (node (ref "IC12") (pin "40") (pinfunction "P0.28/AIN4_40") (pintype "bidirectional"))
    )
    (net (code "63") (name "PG") (class "Default")
      (node (ref "JP9") (pin "2") (pinfunction "2_2") (pintype "passive"))
      (node (ref "Q1") (pin "1") (pinfunction "G_1") (pintype "bidirectional"))
    )
    (net (code "64") (name "PWM-CHG") (class "Default")
      (node (ref "IC12") (pin "20") (pinfunction "P0.17_20") (pintype "bidirectional"))
      (node (ref "JP10") (pin "2") (pinfunction "2_2") (pintype "passive"))
      (node (ref "JP5") (pin "3") (pinfunction "3_3") (pintype "passive"))
    )
    (net (code "65") (name "SCK") (class "Default")
      (node (ref "IC12") (pin "43") (pinfunction "P0.31/AIN7_43") (pintype "bidirectional"))
    )
    (net (code "66") (name "SWDCLK") (class "Default")
      (node (ref "DEBUG1") (pin "4") (pinfunction "SWDCLK/TCK_4") (pintype "bidirectional"))
      (node (ref "IC12") (pin "25") (pinfunction "SWDCLK_25") (pintype "bidirectional"))
      (node (ref "R49") (pin "2") (pinfunction "2_2") (pintype "passive"))
    )
    (net (code "67") (name "SWDIO") (class "Default")
      (node (ref "DEBUG1") (pin "2") (pinfunction "SWDIO/TMS_2") (pintype "bidirectional"))
      (node (ref "IC12") (pin "26") (pinfunction "SWDIO_26") (pintype "bidirectional"))
    )
    (net (code "68") (name "SWO{slash}TDO") (class "Default")
      (node (ref "DEBUG1") (pin "6") (pinfunction "SWO/TDO_6") (pintype "bidirectional"))
      (node (ref "IC12") (pin "21") (pinfunction "P0.18_21") (pintype "bidirectional"))
    )
    (net (code "69") (name "V-ICHG") (class "Default")
      (node (ref "D1") (pin "A") (pinfunction "A_A") (pintype "passive"))
      (node (ref "IC4") (pin "1") (pinfunction "OUT_1") (pintype "output"))
      (node (ref "JP14") (pin "2") (pinfunction "2_2") (pintype "passive"))
      (node (ref "R5") (pin "2") (pinfunction "2_2") (pintype "passive"))
    )
    (net (code "70") (name "V-VCHG") (class "Default")
      (node (ref "C7") (pin "1") (pinfunction "P$1_1") (pintype "passive"))
      (node (ref "D2") (pin "A") (pinfunction "A_A") (pintype "passive"))
      (node (ref "JP13") (pin "2") (pinfunction "2_2") (pintype "passive"))
      (node (ref "R11") (pin "1") (pinfunction "1_1") (pintype "passive"))
      (node (ref "R12") (pin "1") (pinfunction "1_1") (pintype "passive"))
    )
    (net (code "71") (name "VCHG") (class "Default")
      (node (ref "C4") (pin "+") (pinfunction "+_+") (pintype "passive"))
      (node (ref "JP2") (pin "3") (pinfunction "3_3") (pintype "passive"))
      (node (ref "JP3") (pin "1") (pinfunction "1_1") (pintype "passive"))
      (node (ref "JP4") (pin "1") (pinfunction "1_1") (pintype "passive"))
      (node (ref "LS2") (pin "3") (pinfunction "VIN_3") (pintype "input"))
    )
    (net (code "72") (name "VDD_BLE") (class "Default")
      (node (ref "C10") (pin "1") (pinfunction "P$1_1") (pintype "passive"))
      (node (ref "C8") (pin "1") (pinfunction "P$1_1") (pintype "passive"))
      (node (ref "C9") (pin "1") (pinfunction "P$1_1") (pintype "passive"))
      (node (ref "DEBUG1") (pin "1") (pinfunction "VCC_1") (pintype "bidirectional"))
      (node (ref "IC12") (pin "13") (pinfunction "VDD_13") (pintype "bidirectional"))
      (node (ref "IC12") (pin "36") (pinfunction "VDD_36") (pintype "bidirectional"))
      (node (ref "IC12") (pin "48") (pinfunction "VDD_48") (pintype "bidirectional"))
      (node (ref "JP4") (pin "2") (pinfunction "2_2") (pintype "passive"))
      (node (ref "LS3") (pin "3") (pinfunction "VIN_3") (pintype "input"))
      (node (ref "R6") (pin "2") (pinfunction "2_2") (pintype "passive"))
      (node (ref "R60") (pin "1") (pinfunction "1_1") (pintype "passive"))
    )
    (net (code "73") (name "VDD_SENS") (class "Default")
      (node (ref "LS3") (pin "1") (pinfunction "VOUT_1") (pintype "output"))
      (node (ref "SENS") (pin "1") (pinfunction "1_1") (pintype "passive"))
    )
    (net (code "74") (name "VDD_WPT") (class "Default")
      (node (ref "C15") (pin "1") (pinfunction "P$1_1") (pintype "passive"))
      (node (ref "D5") (pin "C") (pinfunction "C_C") (pintype "passive"))
      (node (ref "D8") (pin "C") (pinfunction "C_C") (pintype "passive"))
      (node (ref "D9") (pin "C") (pinfunction "C_C") (pintype "passive"))
      (node (ref "Q2") (pin "4") (pinfunction "S_4") (pintype "passive"))
      (node (ref "R14") (pin "1") (pinfunction "1_1") (pintype "passive"))
      (node (ref "R16") (pin "1") (pinfunction "1_1") (pintype "passive"))
      (node (ref "R8") (pin "1") (pinfunction "1_1") (pintype "passive"))
    )
    (net (code "75") (name "VIN") (class "Default")
      (node (ref "C1") (pin "1") (pinfunction "P$1_1") (pintype "passive"))
      (node (ref "IC1") (pin "1") (pinfunction "VIN_1") (pintype "power_in"))
      (node (ref "IC3") (pin "3") (pinfunction "VIN_3") (pintype "input"))
      (node (ref "Q2") (pin "1") (pinfunction "D_1") (pintype "passive"))
      (node (ref "Q2") (pin "2") (pinfunction "D_2") (pintype "passive"))
      (node (ref "Q2") (pin "5") (pinfunction "D_5") (pintype "passive"))
      (node (ref "Q2") (pin "6") (pinfunction "D_6") (pintype "passive"))
    )
    (net (code "76") (name "VMEAS") (class "Default")
      (node (ref "JP2") (pin "2") (pinfunction "2_2") (pintype "passive"))
      (node (ref "LS1") (pin "1") (pinfunction "VOUT_1") (pintype "output"))
      (node (ref "LS2") (pin "1") (pinfunction "VOUT_1") (pintype "output"))
      (node (ref "R11") (pin "2") (pinfunction "2_2") (pintype "passive"))
    )
    (net (code "77") (name "WAKE-UP") (class "Default")
      (node (ref "D4") (pin "C") (pinfunction "C_C") (pintype "passive"))
      (node (ref "JP11") (pin "2") (pinfunction "2_2") (pintype "passive"))
      (node (ref "R16") (pin "2") (pinfunction "2_2") (pintype "passive"))
    )
    (net (code "78") (name "unconnected-(DEBUG1-KEY-Pad7)") (class "Default")
      (node (ref "DEBUG1") (pin "7") (pinfunction "KEY_7") (pintype "bidirectional"))
    )
    (net (code "79") (name "unconnected-(DEBUG1-NC{slash}TDI-Pad8)") (class "Default")
      (node (ref "DEBUG1") (pin "8") (pinfunction "NC/TDI_8") (pintype "bidirectional"))
    )
    (net (code "80") (name "unconnected-(IC12-NC-Pad44)") (class "Default")
      (node (ref "IC12") (pin "44") (pinfunction "NC_44") (pintype "bidirectional"))
    )
    (net (code "81") (name "~{RESET}") (class "Default")
      (node (ref "C22") (pin "1") (pinfunction "P$1_1") (pintype "passive"))
      (node (ref "DEBUG1") (pin "10") (pinfunction "~{RESET}_10") (pintype "bidirectional"))
      (node (ref "IC12") (pin "24") (pinfunction "P0.21/RESET_24") (pintype "bidirectional"))
      (node (ref "R60") (pin "2") (pinfunction "2_2") (pintype "passive"))
    )
  )
)
